# BreaV5.net
KiCad netlist of a schematic drawn in EAGLE
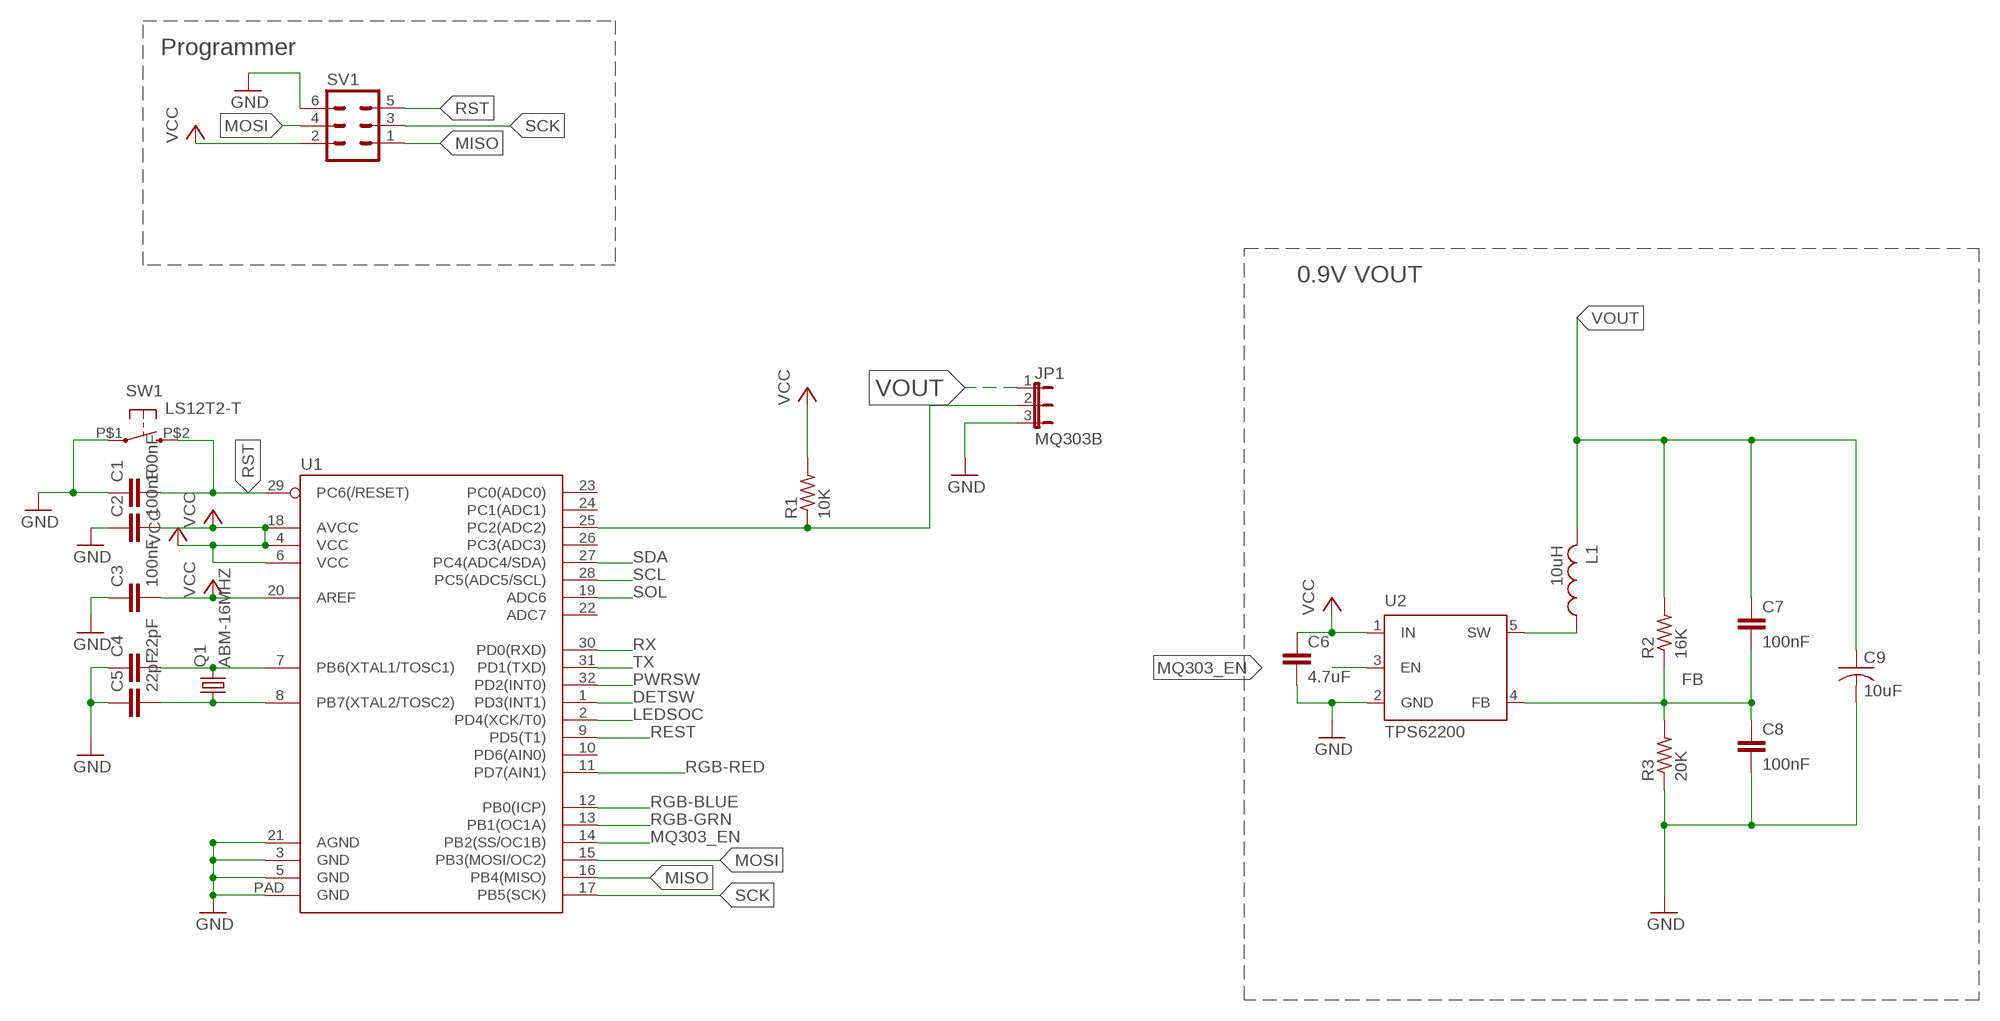
[diagram p0: schematic, sheet 1]
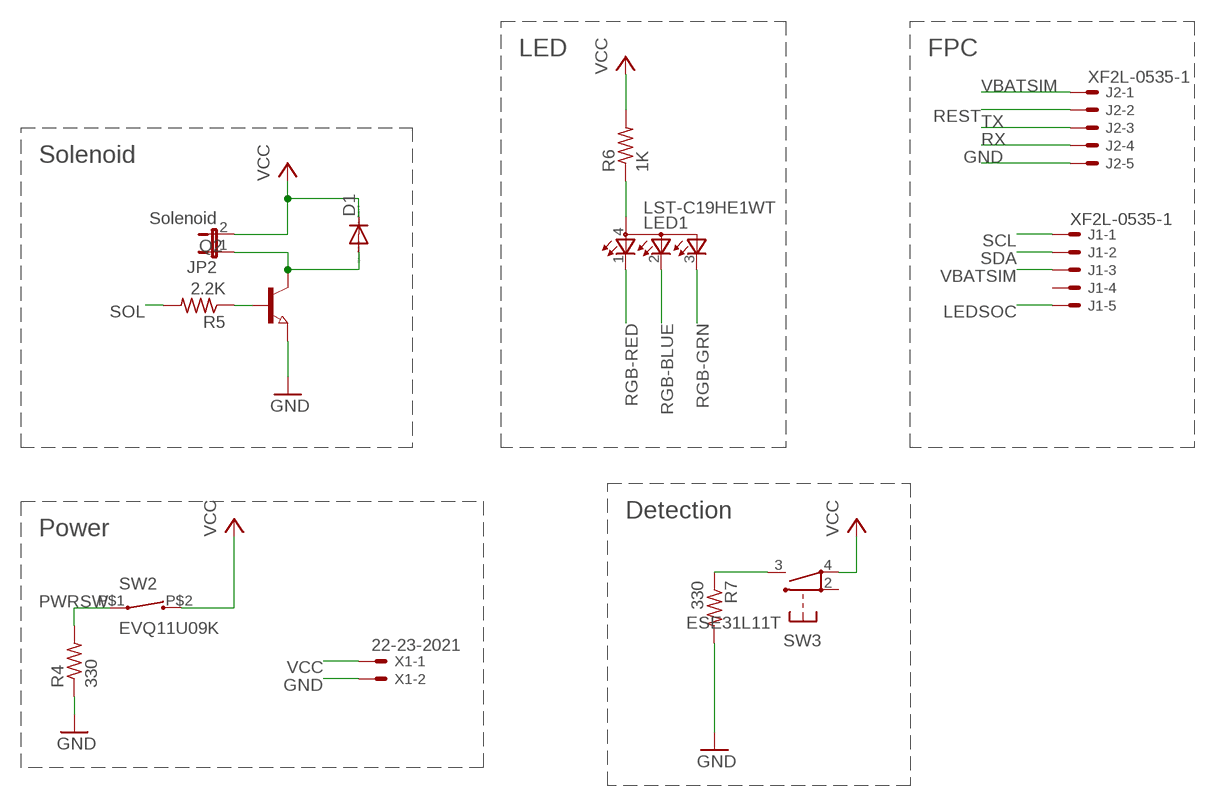
[diagram p1: schematic, sheet 2]

(export (version "E")
  (design (tool "Eeschema 10.0.6"))
  (components
    (comp (ref "D1")
      (value "DIODE-SOD123")
      (footprint "eagle-import:SOD123")
      (libsource (lib "eagle-import") (part "DIODE-SOD123"))
    )
    (comp (ref "J1")
      (value "XF2L-0535-1")
      (footprint "eagle-import:XF2L-0535-1")
      (libsource (lib "eagle-import") (part "XF2-05?35-1L"))
    )
    (comp (ref "J2")
      (value "XF2L-0535-1")
      (footprint "eagle-import:XF2L-0535-1")
      (libsource (lib "eagle-import") (part "XF2-05?35-1L"))
    )
    (comp (ref "JP2")
      (value "Solenoid")
      (footprint "eagle-import:JP1")
      (libsource (lib "eagle-import") (part "JP1E"))
    )
    (comp (ref "LED1")
      (value "LST-C19HE1WT")
      (footprint "eagle-import:LST-C19HE1WT")
      (libsource (lib "eagle-import") (part "LST-C19HE1WT"))
    )
    (comp (ref "Q2")
      (value "NPN-TRANSISTOR_SOT23")
      (footprint "eagle-import:SOT23")
      (libsource (lib "eagle-import") (part "NPN-TRANSISTOR_SOT23"))
    )
    (comp (ref "R4")
      (value "330")
      (footprint "eagle-import:R0402")
      (libsource (lib "eagle-import") (part "R-US_R0402"))
    )
    (comp (ref "R5")
      (value "2.2K")
      (footprint "eagle-import:R0402")
      (libsource (lib "eagle-import") (part "R-US_R0402"))
    )
    (comp (ref "R6")
      (value "1K")
      (footprint "eagle-import:R0402")
      (libsource (lib "eagle-import") (part "R-US_R0402"))
    )
    (comp (ref "R7")
      (value "330")
      (footprint "eagle-import:R0402")
      (libsource (lib "eagle-import") (part "R-US_R0402"))
    )
    (comp (ref "SW2")
      (value "EVQ11U09K")
      (footprint "eagle-import:EVQ11U-09K")
      (libsource (lib "eagle-import") (part "EVQ11U09K"))
    )
    (comp (ref "SW3")
      (value "ESE31L11T")
      (footprint "eagle-import:SWITCH")
      (libsource (lib "eagle-import") (part "ESE31L11T"))
    )
    (comp (ref "X1")
      (value "22-23-2021")
      (footprint "eagle-import:22-23-2021")
      (fields (field (name "MF") "MOLEX"))
      (libsource (lib "eagle-import") (part "22-23-2021"))
    )
    (comp (ref "C1")
      (value "100nF")
      (footprint "eagle-import:C0603")
      (libsource (lib "eagle-import") (part "C-EUC0603"))
    )
    (comp (ref "C2")
      (value "100nF")
      (footprint "eagle-import:C0603")
      (libsource (lib "eagle-import") (part "C-EUC0603"))
    )
    (comp (ref "C3")
      (value "100nF")
      (footprint "eagle-import:C0603")
      (libsource (lib "eagle-import") (part "C-EUC0603"))
    )
    (comp (ref "C4")
      (value "22pF")
      (footprint "eagle-import:C0603")
      (libsource (lib "eagle-import") (part "C-EUC0603"))
    )
    (comp (ref "C5")
      (value "22pF")
      (footprint "eagle-import:C0603")
      (libsource (lib "eagle-import") (part "C-EUC0603"))
    )
    (comp (ref "C6")
      (value "4.7uF")
      (footprint "eagle-import:C0402")
      (libsource (lib "eagle-import") (part "C-EUC0402"))
    )
    (comp (ref "C7")
      (value "100nF")
      (footprint "eagle-import:C0402")
      (libsource (lib "eagle-import") (part "C-EUC0402"))
    )
    (comp (ref "C8")
      (value "100nF")
      (footprint "eagle-import:C0402")
      (libsource (lib "eagle-import") (part "C-EUC0402"))
    )
    (comp (ref "C9")
      (value "10uF")
      (footprint "eagle-import:C0805K")
      (libsource (lib "eagle-import") (part "C-USC0805K"))
    )
    (comp (ref "JP1")
      (value "MQ303B")
      (footprint "eagle-import:JP2")
      (libsource (lib "eagle-import") (part "JP2E"))
    )
    (comp (ref "L1")
      (value "10uH")
      (footprint "eagle-import:L2825P")
      (libsource (lib "eagle-import") (part "L-USL2825P"))
    )
    (comp (ref "Q1")
      (value "ABM-16MHZ")
      (footprint "eagle-import:ABM-16MHZ")
      (libsource (lib "eagle-import") (part "ABM-16MHZ"))
    )
    (comp (ref "R1")
      (value "10K")
      (footprint "eagle-import:R0402")
      (libsource (lib "eagle-import") (part "R-US_R0402"))
    )
    (comp (ref "R2")
      (value "16K")
      (footprint "eagle-import:R0402")
      (libsource (lib "eagle-import") (part "R-US_R0402"))
    )
    (comp (ref "R3")
      (value "20K")
      (footprint "eagle-import:R0402")
      (libsource (lib "eagle-import") (part "R-US_R0402"))
    )
    (comp (ref "SV1")
      (value "MA03-2")
      (footprint "eagle-import:MA03-2")
      (libsource (lib "eagle-import") (part "MA03-2"))
    )
    (comp (ref "SW1")
      (value "LS12T2-T")
      (footprint "eagle-import:LS12T2-T")
      (libsource (lib "eagle-import") (part "LS12T2-T"))
    )
    (comp (ref "U1")
      (value "ATMEGA328P_MLFMLF32")
      (footprint "eagle-import:MLF32-PAD")
      (libsource (lib "eagle-import") (part "ATMEGA328P_MLFMLF32"))
    )
    (comp (ref "U2")
      (value "TPS62200")
      (footprint "eagle-import:TPS62200")
      (libsource (lib "eagle-import") (part "TPS62200"))
    )
  )
  (nets
    (net (code "1") (name "DETSW") (class "Default")
      (node (ref "R7") (pin "1") (pinfunction "1_1") (pintype "passive"))
      (node (ref "SW3") (pin "3") (pinfunction "1_3") (pintype "passive"))
      (node (ref "U1") (pin "1") (pinfunction "PD3(INT1)_1") (pintype "bidirectional"))
    )
    (net (code "2") (name "FB") (class "Default")
      (node (ref "C7") (pin "2") (pinfunction "2_2") (pintype "passive"))
      (node (ref "C8") (pin "1") (pinfunction "1_1") (pintype "passive"))
      (node (ref "R2") (pin "1") (pinfunction "1_1") (pintype "passive"))
      (node (ref "R3") (pin "2") (pinfunction "2_2") (pintype "passive"))
      (node (ref "U2") (pin "4") (pinfunction "FB_4") (pintype "passive"))
    )
    (net (code "3") (name "GND") (class "Default")
      (node (ref "C1") (pin "1") (pinfunction "1_1") (pintype "passive"))
      (node (ref "C2") (pin "1") (pinfunction "1_1") (pintype "passive"))
      (node (ref "C3") (pin "1") (pinfunction "1_1") (pintype "passive"))
      (node (ref "C4") (pin "1") (pinfunction "1_1") (pintype "passive"))
      (node (ref "C5") (pin "1") (pinfunction "1_1") (pintype "passive"))
      (node (ref "C6") (pin "2") (pinfunction "2_2") (pintype "passive"))
      (node (ref "C8") (pin "2") (pinfunction "2_2") (pintype "passive"))
      (node (ref "C9") (pin "2") (pinfunction "2_2") (pintype "passive"))
      (node (ref "J2") (pin "5") (pinfunction "MS_5") (pintype "passive"))
      (node (ref "JP1") (pin "3") (pinfunction "3_3") (pintype "passive"))
      (node (ref "Q2") (pin "2") (pinfunction "E_2") (pintype "passive"))
      (node (ref "R3") (pin "1") (pinfunction "1_1") (pintype "passive"))
      (node (ref "R4") (pin "1") (pinfunction "1_1") (pintype "passive"))
      (node (ref "R7") (pin "2") (pinfunction "2_2") (pintype "passive"))
      (node (ref "SV1") (pin "6") (pinfunction "MISO_6") (pintype "passive"))
      (node (ref "SW1") (pin "P$1") (pinfunction "S1_P$1") (pintype "passive"))
      (node (ref "U1") (pin "21") (pinfunction "AGND_21") (pintype "bidirectional"))
      (node (ref "U1") (pin "3") (pinfunction "GND_3") (pintype "bidirectional"))
      (node (ref "U1") (pin "5") (pinfunction "GND_5") (pintype "bidirectional"))
      (node (ref "U1") (pin "PAD") (pinfunction "GND_PAD") (pintype "bidirectional"))
      (node (ref "U2") (pin "2") (pinfunction "GND_2") (pintype "power_in"))
      (node (ref "X1") (pin "2") (pinfunction "S_2") (pintype "passive"))
    )
    (net (code "4") (name "LEDSOC") (class "Default")
      (node (ref "J1") (pin "5") (pinfunction "MS_5") (pintype "passive"))
      (node (ref "U1") (pin "2") (pinfunction "PD4(XCK/T0)_2") (pintype "bidirectional"))
    )
    (net (code "5") (name "MISO") (class "Default")
      (node (ref "SV1") (pin "1") (pinfunction "1_1") (pintype "passive"))
      (node (ref "U1") (pin "16") (pinfunction "PB4(MISO)_16") (pintype "bidirectional"))
    )
    (net (code "6") (name "MOSI") (class "Default")
      (node (ref "SV1") (pin "4") (pinfunction "4_4") (pintype "passive"))
      (node (ref "U1") (pin "15") (pinfunction "PB3(MOSI/OC2)_15") (pintype "bidirectional"))
    )
    (net (code "7") (name "MQ303_EN") (class "Default")
      (node (ref "U1") (pin "14") (pinfunction "PB2(SS/OC1B)_14") (pintype "bidirectional"))
      (node (ref "U2") (pin "3") (pinfunction "EN_3") (pintype "input"))
    )
    (net (code "8") (name "Net-(LED1-A)") (class "Default")
      (node (ref "LED1") (pin "4") (pinfunction "A_4") (pintype "passive"))
      (node (ref "R6") (pin "1") (pinfunction "1_1") (pintype "passive"))
    )
    (net (code "9") (name "Net-(Q1-1)") (class "Default")
      (node (ref "C5") (pin "2") (pinfunction "2_2") (pintype "passive"))
      (node (ref "Q1") (pin "P$1") (pinfunction "1_P$1") (pintype "passive"))
      (node (ref "U1") (pin "8") (pinfunction "PB7(XTAL2/TOSC2)_8") (pintype "bidirectional"))
    )
    (net (code "10") (name "Net-(Q1-2)") (class "Default")
      (node (ref "C4") (pin "2") (pinfunction "2_2") (pintype "passive"))
      (node (ref "Q1") (pin "P$2") (pinfunction "2_P$2") (pintype "passive"))
      (node (ref "U1") (pin "7") (pinfunction "PB6(XTAL1/TOSC1)_7") (pintype "bidirectional"))
    )
    (net (code "11") (name "Net-(Q2-B)") (class "Default")
      (node (ref "Q2") (pin "1") (pinfunction "B_1") (pintype "passive"))
      (node (ref "R5") (pin "1") (pinfunction "1_1") (pintype "passive"))
    )
    (net (code "12") (name "Net-(Q2-C)") (class "Default")
      (node (ref "D1") (pin "A") (pinfunction "A_A") (pintype "passive"))
      (node (ref "JP2") (pin "1") (pinfunction "1_1") (pintype "passive"))
      (node (ref "Q2") (pin "3") (pinfunction "C_3") (pintype "passive"))
    )
    (net (code "13") (name "Net-(U1-PC2(ADC2))") (class "Default")
      (node (ref "JP1") (pin "2") (pinfunction "2_2") (pintype "passive"))
      (node (ref "R1") (pin "1") (pinfunction "1_1") (pintype "passive"))
      (node (ref "U1") (pin "25") (pinfunction "PC2(ADC2)_25") (pintype "bidirectional"))
    )
    (net (code "14") (name "Net-(U2-SW)") (class "Default")
      (node (ref "L1") (pin "1") (pinfunction "1_1") (pintype "passive"))
      (node (ref "U2") (pin "5") (pinfunction "SW_5") (pintype "passive"))
    )
    (net (code "15") (name "PWRSW") (class "Default")
      (node (ref "R4") (pin "2") (pinfunction "2_2") (pintype "passive"))
      (node (ref "SW2") (pin "P$1") (pinfunction "1_P$1") (pintype "passive"))
      (node (ref "U1") (pin "32") (pinfunction "PD2(INT0)_32") (pintype "bidirectional"))
    )
    (net (code "16") (name "REST") (class "Default")
      (node (ref "J2") (pin "2") (pinfunction "MS_2") (pintype "passive"))
      (node (ref "U1") (pin "9") (pinfunction "PD5(T1)_9") (pintype "bidirectional"))
    )
    (net (code "17") (name "RGB-BLUE") (class "Default")
      (node (ref "LED1") (pin "2") (pinfunction "CGREEN_2") (pintype "passive"))
      (node (ref "U1") (pin "12") (pinfunction "PB0(ICP)_12") (pintype "bidirectional"))
    )
    (net (code "18") (name "RGB-GRN") (class "Default")
      (node (ref "LED1") (pin "3") (pinfunction "CBLUE_3") (pintype "passive"))
      (node (ref "U1") (pin "13") (pinfunction "PB1(OC1A)_13") (pintype "bidirectional"))
    )
    (net (code "19") (name "RGB-RED") (class "Default")
      (node (ref "LED1") (pin "1") (pinfunction "CRED_1") (pintype "passive"))
      (node (ref "U1") (pin "11") (pinfunction "PD7(AIN1)_11") (pintype "bidirectional"))
    )
    (net (code "20") (name "RST") (class "Default")
      (node (ref "C1") (pin "2") (pinfunction "2_2") (pintype "passive"))
      (node (ref "SV1") (pin "5") (pinfunction "VTG_5") (pintype "passive"))
      (node (ref "SW1") (pin "P$2") (pinfunction "S2_P$2") (pintype "passive"))
      (node (ref "U1") (pin "29") (pinfunction "PC6(/RESET)_29") (pintype "bidirectional"))
    )
    (net (code "21") (name "RX") (class "Default")
      (node (ref "J2") (pin "4") (pinfunction "MS_4") (pintype "passive"))
      (node (ref "U1") (pin "30") (pinfunction "PD0(RXD)_30") (pintype "bidirectional"))
    )
    (net (code "22") (name "SCK") (class "Default")
      (node (ref "SV1") (pin "3") (pinfunction "3_3") (pintype "passive"))
      (node (ref "U1") (pin "17") (pinfunction "PB5(SCK)_17") (pintype "bidirectional"))
    )
    (net (code "23") (name "SCL") (class "Default")
      (node (ref "J1") (pin "1") (pinfunction "MSV_1") (pintype "passive"))
      (node (ref "U1") (pin "28") (pinfunction "PC5(ADC5/SCL)_28") (pintype "bidirectional"))
    )
    (net (code "24") (name "SDA") (class "Default")
      (node (ref "J1") (pin "2") (pinfunction "MS_2") (pintype "passive"))
      (node (ref "U1") (pin "27") (pinfunction "PC4(ADC4/SDA)_27") (pintype "bidirectional"))
    )
    (net (code "25") (name "SOL") (class "Default")
      (node (ref "R5") (pin "2") (pinfunction "2_2") (pintype "passive"))
      (node (ref "U1") (pin "19") (pinfunction "ADC6_19") (pintype "bidirectional"))
    )
    (net (code "26") (name "TX") (class "Default")
      (node (ref "J2") (pin "3") (pinfunction "MS_3") (pintype "passive"))
      (node (ref "U1") (pin "31") (pinfunction "PD1(TXD)_31") (pintype "bidirectional"))
    )
    (net (code "27") (name "VBATSIM") (class "Default")
      (node (ref "J1") (pin "3") (pinfunction "MS_3") (pintype "passive"))
      (node (ref "J2") (pin "1") (pinfunction "MSV_1") (pintype "passive"))
    )
    (net (code "28") (name "VCC") (class "Default")
      (node (ref "C2") (pin "2") (pinfunction "2_2") (pintype "passive"))
      (node (ref "C3") (pin "2") (pinfunction "2_2") (pintype "passive"))
      (node (ref "C6") (pin "1") (pinfunction "1_1") (pintype "passive"))
      (node (ref "D1") (pin "C") (pinfunction "C_C") (pintype "passive"))
      (node (ref "JP2") (pin "2") (pinfunction "2_2") (pintype "passive"))
      (node (ref "R1") (pin "2") (pinfunction "2_2") (pintype "passive"))
      (node (ref "R6") (pin "2") (pinfunction "2_2") (pintype "passive"))
      (node (ref "SV1") (pin "2") (pinfunction "2_2") (pintype "passive"))
      (node (ref "SW2") (pin "P$2") (pinfunction "2_P$2") (pintype "passive"))
      (node (ref "SW3") (pin "4") (pinfunction "C3_4") (pintype "passive"))
      (node (ref "U1") (pin "18") (pinfunction "AVCC_18") (pintype "bidirectional"))
      (node (ref "U1") (pin "20") (pinfunction "AREF_20") (pintype "bidirectional"))
      (node (ref "U1") (pin "4") (pinfunction "VCC_4") (pintype "bidirectional"))
      (node (ref "U1") (pin "6") (pinfunction "VCC_6") (pintype "bidirectional"))
      (node (ref "U2") (pin "1") (pinfunction "IN_1") (pintype "input"))
      (node (ref "X1") (pin "1") (pinfunction "S_1") (pintype "passive"))
    )
    (net (code "29") (name "VOUT") (class "Default")
      (node (ref "C7") (pin "1") (pinfunction "1_1") (pintype "passive"))
      (node (ref "C9") (pin "1") (pinfunction "1_1") (pintype "passive"))
      (node (ref "JP1") (pin "1") (pinfunction "1_1") (pintype "passive"))
      (node (ref "L1") (pin "2") (pinfunction "2_2") (pintype "passive"))
      (node (ref "R2") (pin "2") (pinfunction "2_2") (pintype "passive"))
    )
    (net (code "30") (name "unconnected-(J1D-MS-Pad4)") (class "Default")
      (node (ref "J1") (pin "4") (pinfunction "MS_4") (pintype "passive"))
    )
    (net (code "31") (name "unconnected-(SW3-C2-Pad2)") (class "Default")
      (node (ref "SW3") (pin "2") (pinfunction "C2_2") (pintype "passive"))
    )
    (net (code "32") (name "unconnected-(U1-ADC7-Pad22)") (class "Default")
      (node (ref "U1") (pin "22") (pinfunction "ADC7_22") (pintype "bidirectional"))
    )
    (net (code "33") (name "unconnected-(U1-PC0(ADC0)-Pad23)") (class "Default")
      (node (ref "U1") (pin "23") (pinfunction "PC0(ADC0)_23") (pintype "bidirectional"))
    )
    (net (code "34") (name "unconnected-(U1-PC1(ADC1)-Pad24)") (class "Default")
      (node (ref "U1") (pin "24") (pinfunction "PC1(ADC1)_24") (pintype "bidirectional"))
    )
    (net (code "35") (name "unconnected-(U1-PC3(ADC3)-Pad26)") (class "Default")
      (node (ref "U1") (pin "26") (pinfunction "PC3(ADC3)_26") (pintype "bidirectional"))
    )
    (net (code "36") (name "unconnected-(U1-PD6(AIN0)-Pad10)") (class "Default")
      (node (ref "U1") (pin "10") (pinfunction "PD6(AIN0)_10") (pintype "bidirectional"))
    )
  )
)
